# base.net
KiCad netlist of a schematic drawn in EAGLE
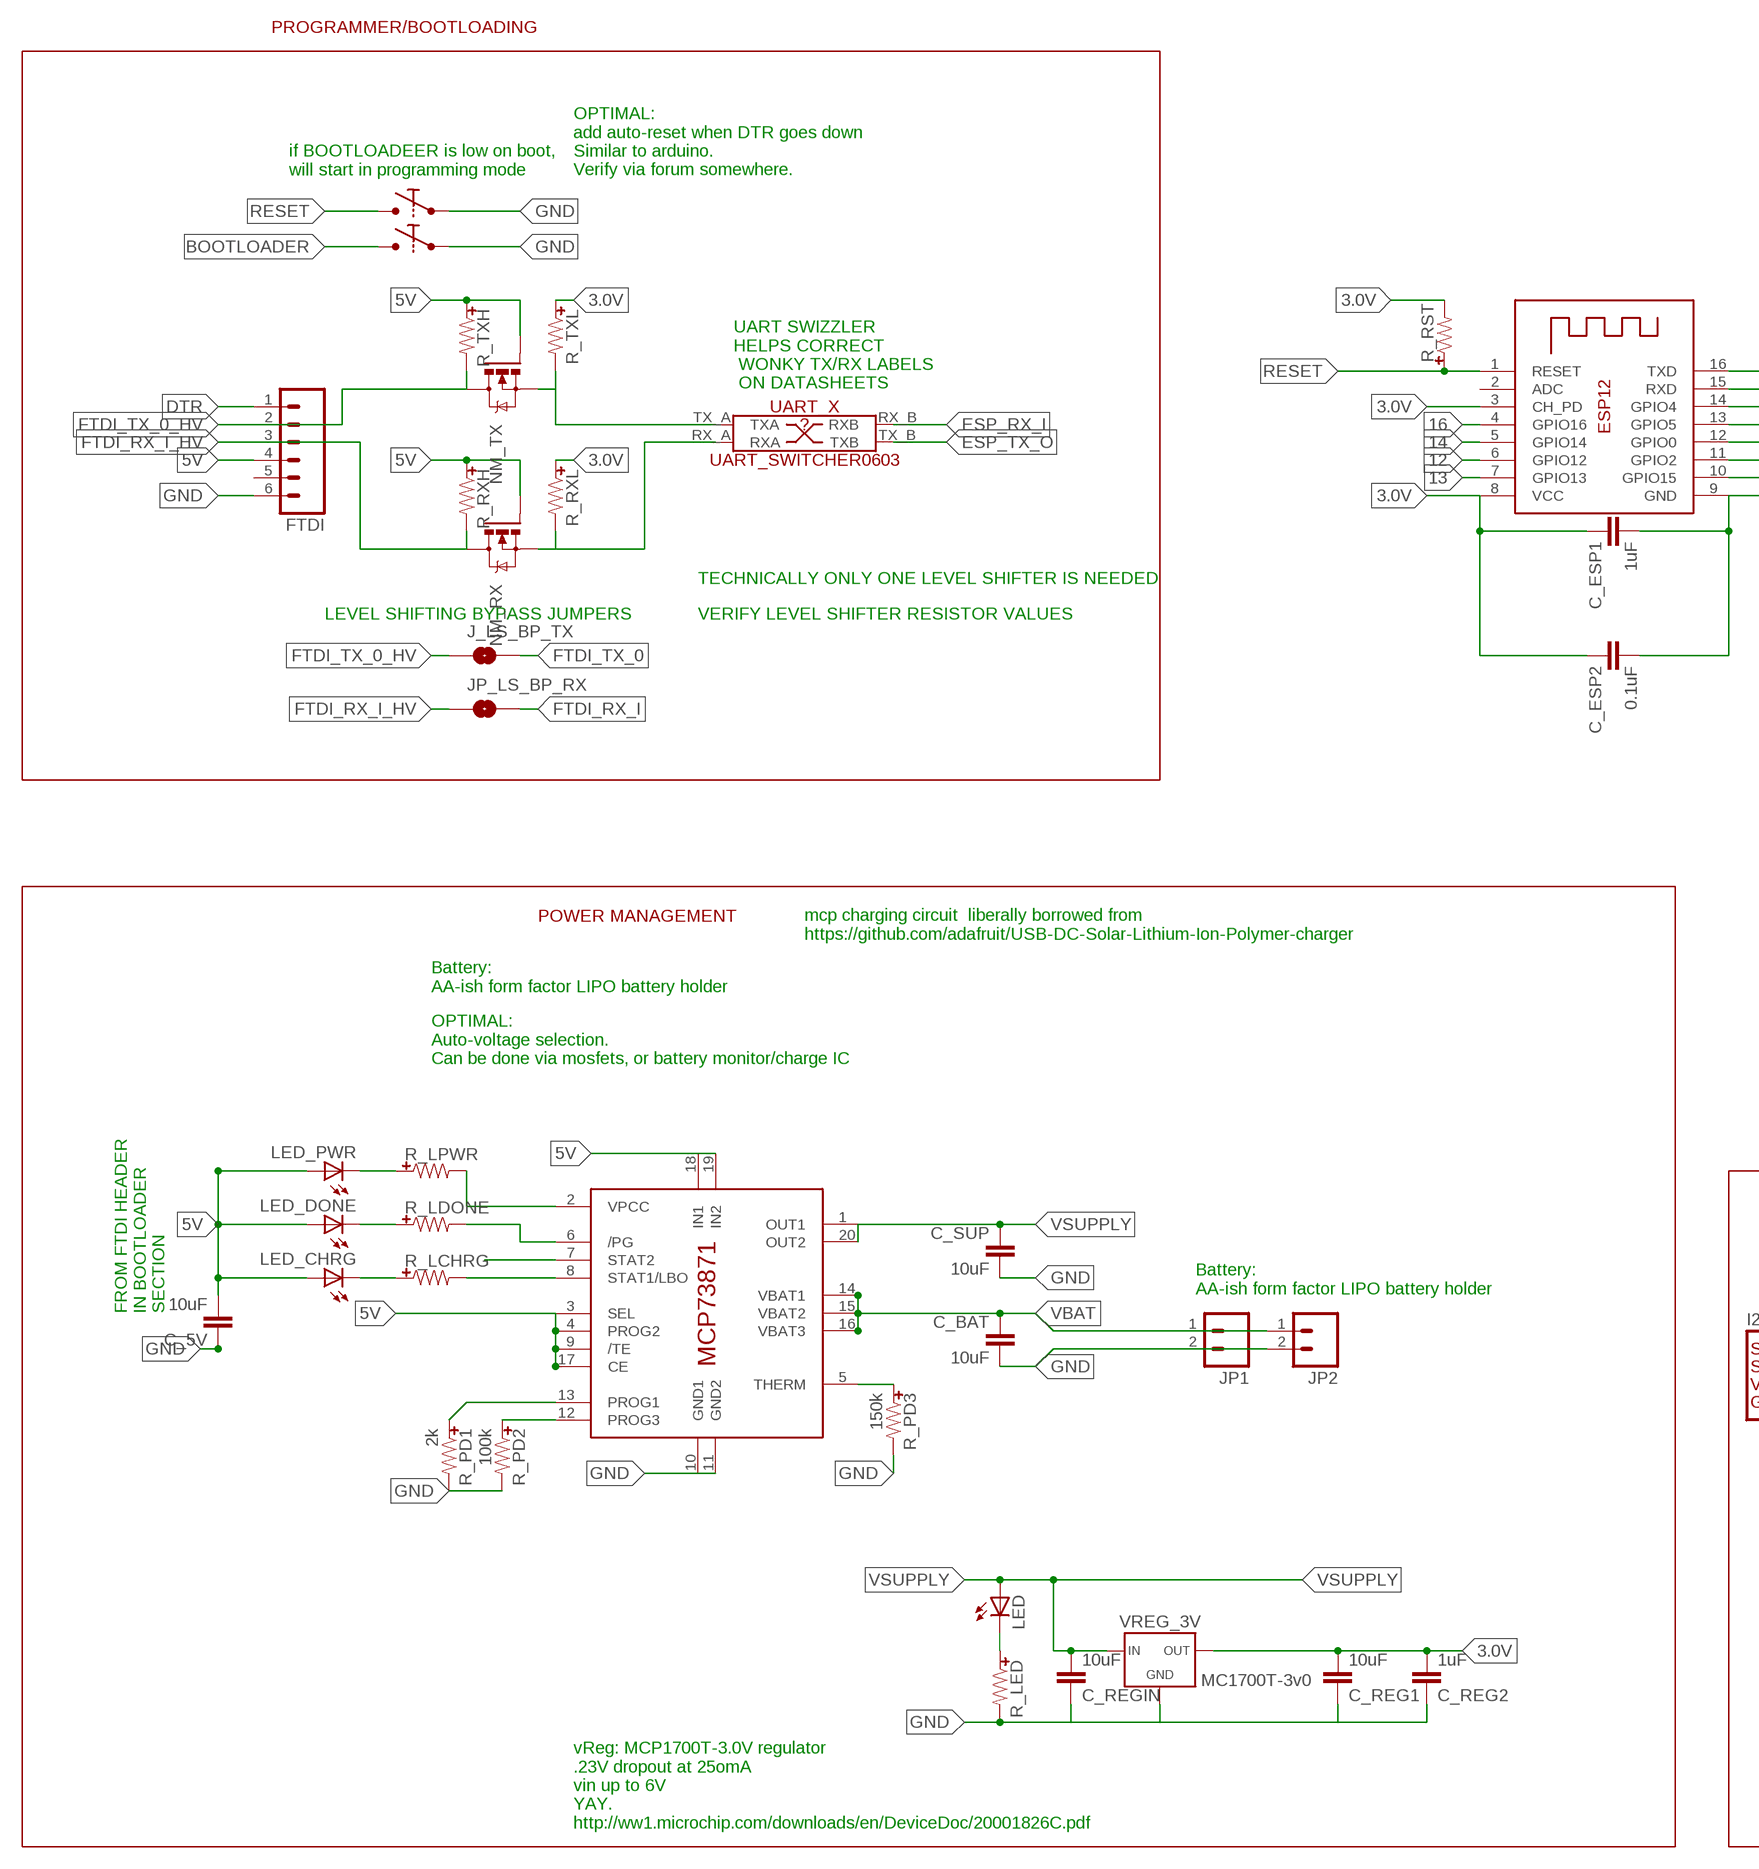
[diagram p0: schematic, sheet 1, part 1 of 2]
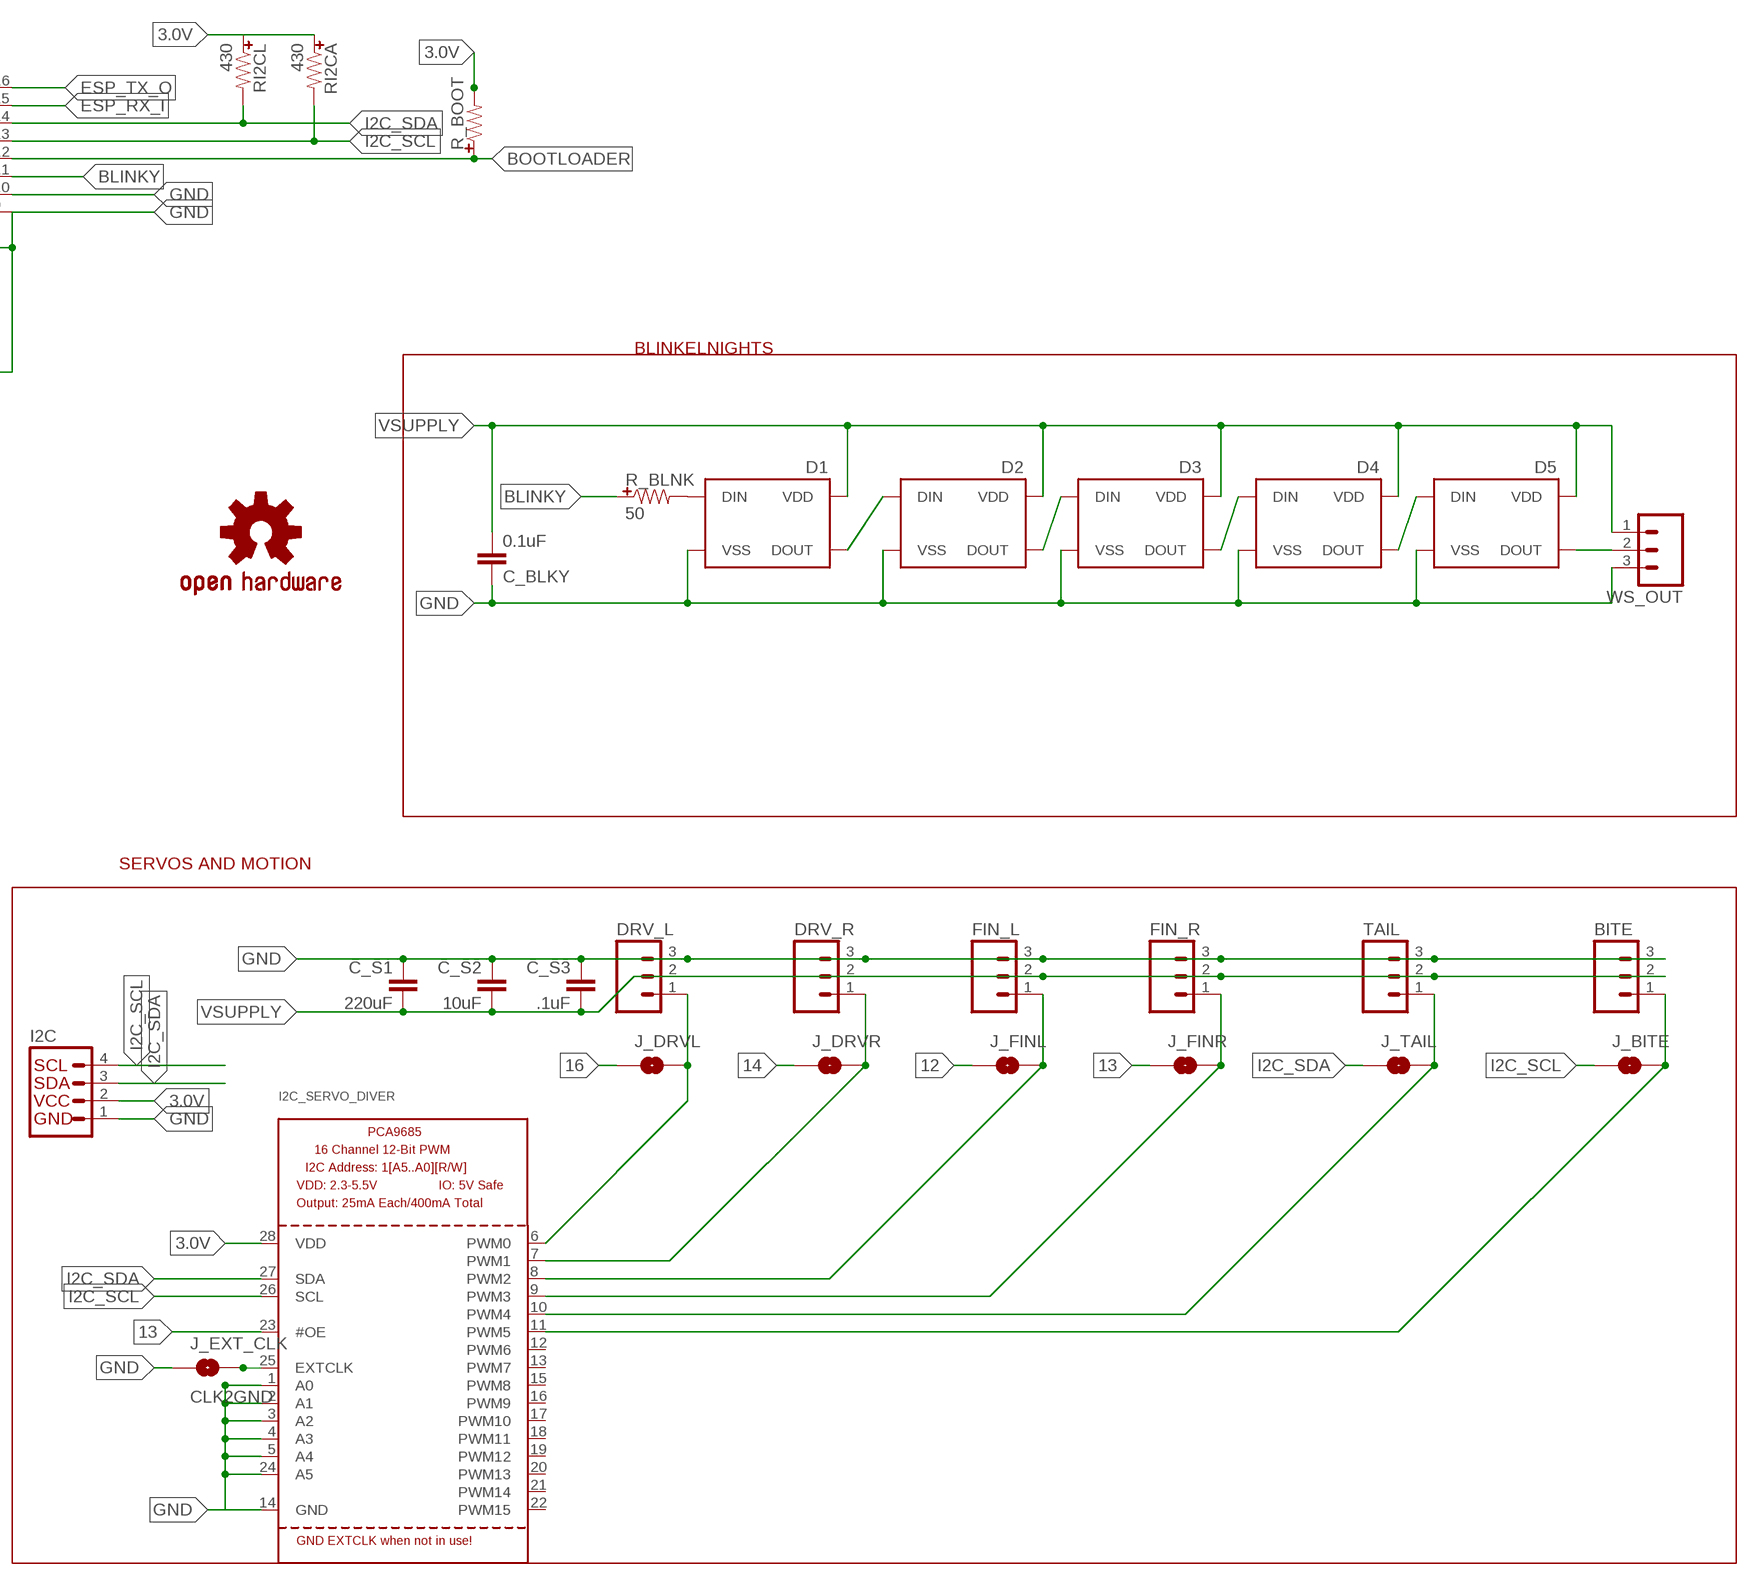
[diagram p1: schematic, sheet 1, part 2 of 2]

(export (version "E")
  (design (tool "Eeschema 10.0.6"))
  (components
    (comp (ref "BITE")
      (value "M03LOCK")
      (footprint "eagle-import:1X03_LOCK")
      (libsource (lib "eagle-import") (part "M03LOCK"))
    )
    (comp (ref "BTN_PROG")
      (value "BUTTONSMD_BUTTON")
      (footprint "eagle-import:SMD_BUTTON")
      (libsource (lib "eagle-import") (part "BUTTONSMD_BUTTON"))
    )
    (comp (ref "BTN_RST")
      (value "BUTTONSMD_BUTTON")
      (footprint "eagle-import:SMD_BUTTON")
      (libsource (lib "eagle-import") (part "BUTTONSMD_BUTTON"))
    )
    (comp (ref "C_5V")
      (value "10uF")
      (footprint "eagle-import:0402-0603-0805-UNIVERSAL")
      (libsource (lib "eagle-import") (part "CAPUNIVERSAL"))
    )
    (comp (ref "C_BAT")
      (value "10uF")
      (footprint "eagle-import:0402-0603-0805-UNIVERSAL")
      (libsource (lib "eagle-import") (part "CAPUNIVERSAL"))
    )
    (comp (ref "C_BLKY")
      (value "0.1uF")
      (footprint "eagle-import:0402-0603-0805-UNIVERSAL")
      (libsource (lib "eagle-import") (part "CAPUNIVERSAL"))
    )
    (comp (ref "C_ESP1")
      (value "1uF")
      (footprint "eagle-import:0402-0603-0805-UNIVERSAL")
      (libsource (lib "eagle-import") (part "CAPUNIVERSAL"))
    )
    (comp (ref "C_ESP2")
      (value "0.1uF")
      (footprint "eagle-import:0402-0603-0805-UNIVERSAL")
      (libsource (lib "eagle-import") (part "CAPUNIVERSAL"))
    )
    (comp (ref "C_REG1")
      (value "10uF")
      (footprint "eagle-import:0402-0603-0805-UNIVERSAL")
      (libsource (lib "eagle-import") (part "CAPUNIVERSAL"))
    )
    (comp (ref "C_REG2")
      (value "1uF")
      (footprint "eagle-import:0402-0603-0805-UNIVERSAL")
      (libsource (lib "eagle-import") (part "CAPUNIVERSAL"))
    )
    (comp (ref "C_REGIN")
      (value "10uF")
      (footprint "eagle-import:0402-0603-0805-UNIVERSAL")
      (libsource (lib "eagle-import") (part "CAPUNIVERSAL"))
    )
    (comp (ref "C_S1")
      (value "220uF")
      (footprint "eagle-import:0402-0603-0805-UNIVERSAL")
      (libsource (lib "eagle-import") (part "CAPUNIVERSAL"))
    )
    (comp (ref "C_S2")
      (value "10uF")
      (footprint "eagle-import:0402-0603-0805-UNIVERSAL")
      (libsource (lib "eagle-import") (part "CAPUNIVERSAL"))
    )
    (comp (ref "C_S3")
      (value ".1uF")
      (footprint "eagle-import:0402-0603-0805-UNIVERSAL")
      (libsource (lib "eagle-import") (part "CAPUNIVERSAL"))
    )
    (comp (ref "C_SUP")
      (value "10uF")
      (footprint "eagle-import:0402-0603-0805-UNIVERSAL")
      (libsource (lib "eagle-import") (part "CAPUNIVERSAL"))
    )
    (comp (ref "D1")
      (value "WS2812B")
      (footprint "eagle-import:WS2812B")
      (libsource (lib "eagle-import") (part "WS2812B"))
    )
    (comp (ref "D2")
      (value "WS2812B")
      (footprint "eagle-import:WS2812B")
      (libsource (lib "eagle-import") (part "WS2812B"))
    )
    (comp (ref "D3")
      (value "WS2812B")
      (footprint "eagle-import:WS2812B")
      (libsource (lib "eagle-import") (part "WS2812B"))
    )
    (comp (ref "D4")
      (value "WS2812B")
      (footprint "eagle-import:WS2812B")
      (libsource (lib "eagle-import") (part "WS2812B"))
    )
    (comp (ref "D5")
      (value "WS2812B")
      (footprint "eagle-import:WS2812B")
      (libsource (lib "eagle-import") (part "WS2812B"))
    )
    (comp (ref "DRV_L")
      (value "M03LOCK")
      (footprint "eagle-import:1X03_LOCK")
      (libsource (lib "eagle-import") (part "M03LOCK"))
    )
    (comp (ref "DRV_R")
      (value "M03LOCK")
      (footprint "eagle-import:1X03_LOCK")
      (libsource (lib "eagle-import") (part "M03LOCK"))
    )
    (comp (ref "FIN_L")
      (value "M03LOCK")
      (footprint "eagle-import:1X03_LOCK")
      (libsource (lib "eagle-import") (part "M03LOCK"))
    )
    (comp (ref "FIN_R")
      (value "M03LOCK")
      (footprint "eagle-import:1X03_LOCK")
      (libsource (lib "eagle-import") (part "M03LOCK"))
    )
    (comp (ref "FTDI")
      (value "M06LOCK")
      (footprint "eagle-import:1X06_LOCK")
      (libsource (lib "eagle-import") (part "M06LOCK"))
    )
    (comp (ref "I2C")
      (value "I2C_STANDARD")
      (footprint "eagle-import:1X04")
      (libsource (lib "eagle-import") (part "I2C_STANDARD"))
    )
    (comp (ref "I2C_SERVO_DIVER")
      (value "PCA9685")
      (footprint "eagle-import:TSSOP28")
      (libsource (lib "eagle-import") (part "PCA9685"))
    )
    (comp (ref "IC_LIPO")
      (value "MCP73871")
      (footprint "eagle-import:QFN20")
      (libsource (lib "eagle-import") (part "MCP73871"))
    )
    (comp (ref "JP1")
      (value "M02JST-PTH-2")
      (footprint "eagle-import:JST-2-PTH")
      (libsource (lib "eagle-import") (part "M02JST-PTH-2"))
    )
    (comp (ref "JP2")
      (value "M02LOCK")
      (footprint "eagle-import:1X02_LOCK")
      (libsource (lib "eagle-import") (part "M02LOCK"))
    )
    (comp (ref "JP_LS_BP_RX")
      (value "JUMPER-PAD-2-NOYES_SILK")
      (footprint "eagle-import:PAD-JUMPER-2-NO_YES_SILK")
      (libsource (lib "eagle-import") (part "JUMPER-PAD-2-NOYES_SILK"))
    )
    (comp (ref "J_BITE")
      (value "JUMPER-PAD-2-NOYES_SILK")
      (footprint "eagle-import:PAD-JUMPER-2-NO_YES_SILK")
      (libsource (lib "eagle-import") (part "JUMPER-PAD-2-NOYES_SILK"))
    )
    (comp (ref "J_DRVL")
      (value "JUMPER-PAD-2-NOYES_SILK")
      (footprint "eagle-import:PAD-JUMPER-2-NO_YES_SILK")
      (libsource (lib "eagle-import") (part "JUMPER-PAD-2-NOYES_SILK"))
    )
    (comp (ref "J_DRVR")
      (value "JUMPER-PAD-2-NOYES_SILK")
      (footprint "eagle-import:PAD-JUMPER-2-NO_YES_SILK")
      (libsource (lib "eagle-import") (part "JUMPER-PAD-2-NOYES_SILK"))
    )
    (comp (ref "J_EXT_CLK")
      (value "CLK2GND")
      (footprint "eagle-import:SJ_2S-TRACE")
      (libsource (lib "eagle-import") (part "SOLDERJUMPERTRACE"))
    )
    (comp (ref "J_FINL")
      (value "JUMPER-PAD-2-NOYES_SILK")
      (footprint "eagle-import:PAD-JUMPER-2-NO_YES_SILK")
      (libsource (lib "eagle-import") (part "JUMPER-PAD-2-NOYES_SILK"))
    )
    (comp (ref "J_FINR")
      (value "JUMPER-PAD-2-NOYES_SILK")
      (footprint "eagle-import:PAD-JUMPER-2-NO_YES_SILK")
      (libsource (lib "eagle-import") (part "JUMPER-PAD-2-NOYES_SILK"))
    )
    (comp (ref "J_LS_BP_TX")
      (value "JUMPER-PAD-2-NOYES_SILK")
      (footprint "eagle-import:PAD-JUMPER-2-NO_YES_SILK")
      (libsource (lib "eagle-import") (part "JUMPER-PAD-2-NOYES_SILK"))
    )
    (comp (ref "J_TAIL")
      (value "JUMPER-PAD-2-NOYES_SILK")
      (footprint "eagle-import:PAD-JUMPER-2-NO_YES_SILK")
      (libsource (lib "eagle-import") (part "JUMPER-PAD-2-NOYES_SILK"))
    )
    (comp (ref "LED")
      (value "LEDUNIVERSAL")
      (footprint "eagle-import:0402-0603-0805-UNIVERSAL")
      (libsource (lib "eagle-import") (part "LEDUNIVERSAL"))
    )
    (comp (ref "LED_CHRG")
      (value "LEDUNIVERSAL")
      (footprint "eagle-import:0402-0603-0805-UNIVERSAL")
      (libsource (lib "eagle-import") (part "LEDUNIVERSAL"))
    )
    (comp (ref "LED_DONE")
      (value "LEDUNIVERSAL")
      (footprint "eagle-import:0402-0603-0805-UNIVERSAL")
      (libsource (lib "eagle-import") (part "LEDUNIVERSAL"))
    )
    (comp (ref "LED_PWR")
      (value "LEDUNIVERSAL")
      (footprint "eagle-import:0402-0603-0805-UNIVERSAL")
      (libsource (lib "eagle-import") (part "LEDUNIVERSAL"))
    )
    (comp (ref "LOGO1")
      (value "OSHW-LOGOS")
      (footprint "eagle-import:OSHW-LOGO-S")
      (libsource (lib "eagle-import") (part "OSHW-LOGOS"))
    )
    (comp (ref "NM_RX")
      (value "MOSFET-NCHANNELSMD")
      (footprint "eagle-import:SOT23-3")
      (libsource (lib "eagle-import") (part "MOSFET-NCHANNELSMD"))
    )
    (comp (ref "NM_TX")
      (value "MOSFET-NCHANNELSMD")
      (footprint "eagle-import:SOT23-3")
      (libsource (lib "eagle-import") (part "MOSFET-NCHANNELSMD"))
    )
    (comp (ref "RI2CA")
      (value "430")
      (footprint "eagle-import:0402-0603-0805-UNIVERSAL")
      (libsource (lib "eagle-import") (part "RESISTORUNIVERSAL"))
    )
    (comp (ref "RI2CL")
      (value "430")
      (footprint "eagle-import:0402-0603-0805-UNIVERSAL")
      (libsource (lib "eagle-import") (part "RESISTORUNIVERSAL"))
    )
    (comp (ref "R_BLNK")
      (value "50")
      (footprint "eagle-import:0402-0603-0805-UNIVERSAL")
      (libsource (lib "eagle-import") (part "RESISTORUNIVERSAL"))
    )
    (comp (ref "R_BOOT")
      (value "RESISTORUNIVERSAL")
      (footprint "eagle-import:0402-0603-0805-UNIVERSAL")
      (libsource (lib "eagle-import") (part "RESISTORUNIVERSAL"))
    )
    (comp (ref "R_LCHRG")
      (value "RESISTORUNIVERSAL")
      (footprint "eagle-import:0402-0603-0805-UNIVERSAL")
      (libsource (lib "eagle-import") (part "RESISTORUNIVERSAL"))
    )
    (comp (ref "R_LDONE")
      (value "RESISTORUNIVERSAL")
      (footprint "eagle-import:0402-0603-0805-UNIVERSAL")
      (libsource (lib "eagle-import") (part "RESISTORUNIVERSAL"))
    )
    (comp (ref "R_LED")
      (value "RESISTORUNIVERSAL")
      (footprint "eagle-import:0402-0603-0805-UNIVERSAL")
      (libsource (lib "eagle-import") (part "RESISTORUNIVERSAL"))
    )
    (comp (ref "R_LPWR")
      (value "RESISTORUNIVERSAL")
      (footprint "eagle-import:0402-0603-0805-UNIVERSAL")
      (libsource (lib "eagle-import") (part "RESISTORUNIVERSAL"))
    )
    (comp (ref "R_PD1")
      (value "2k")
      (footprint "eagle-import:0402-0603-0805-UNIVERSAL")
      (libsource (lib "eagle-import") (part "RESISTORUNIVERSAL"))
    )
    (comp (ref "R_PD2")
      (value "100k")
      (footprint "eagle-import:0402-0603-0805-UNIVERSAL")
      (libsource (lib "eagle-import") (part "RESISTORUNIVERSAL"))
    )
    (comp (ref "R_PD3")
      (value "150k")
      (footprint "eagle-import:0402-0603-0805-UNIVERSAL")
      (libsource (lib "eagle-import") (part "RESISTORUNIVERSAL"))
    )
    (comp (ref "R_RST")
      (value "RESISTORUNIVERSAL")
      (footprint "eagle-import:0402-0603-0805-UNIVERSAL")
      (libsource (lib "eagle-import") (part "RESISTORUNIVERSAL"))
    )
    (comp (ref "R_RXH")
      (value "RESISTORUNIVERSAL")
      (footprint "eagle-import:0402-0603-0805-UNIVERSAL")
      (libsource (lib "eagle-import") (part "RESISTORUNIVERSAL"))
    )
    (comp (ref "R_RXL")
      (value "RESISTORUNIVERSAL")
      (footprint "eagle-import:0402-0603-0805-UNIVERSAL")
      (libsource (lib "eagle-import") (part "RESISTORUNIVERSAL"))
    )
    (comp (ref "R_TXH")
      (value "RESISTORUNIVERSAL")
      (footprint "eagle-import:0402-0603-0805-UNIVERSAL")
      (libsource (lib "eagle-import") (part "RESISTORUNIVERSAL"))
    )
    (comp (ref "R_TXL")
      (value "RESISTORUNIVERSAL")
      (footprint "eagle-import:0402-0603-0805-UNIVERSAL")
      (libsource (lib "eagle-import") (part "RESISTORUNIVERSAL"))
    )
    (comp (ref "TAIL")
      (value "M03LOCK")
      (footprint "eagle-import:1X03_LOCK")
      (libsource (lib "eagle-import") (part "M03LOCK"))
    )
    (comp (ref "UART_X")
      (value "UART_SWITCHER0603")
      (footprint "eagle-import:UART_SWITCHER_0603")
      (libsource (lib "eagle-import") (part "UART_SWITCHER0603"))
    )
    (comp (ref "VREG_3V")
      (value "MC1700T-3v0")
      (footprint "eagle-import:SOT23")
      (libsource (lib "eagle-import") (part "VOLTAGE-REGULATORMCP1703"))
    )
    (comp (ref "WS_OUT")
      (value "M03LOCK")
      (footprint "eagle-import:1X03_LOCK")
      (libsource (lib "eagle-import") (part "M03LOCK"))
    )
    (comp (ref "X1")
      (value "ESP-12")
      (footprint "eagle-import:ESP-12")
      (libsource (lib "eagle-import") (part "ESP-12"))
    )
  )
  (nets
    (net (code "1") (name "3.0V") (class "Default")
      (node (ref "C_ESP1") (pin "-") (pinfunction "1_-") (pintype "passive"))
      (node (ref "C_ESP2") (pin "-") (pinfunction "1_-") (pintype "passive"))
      (node (ref "C_REG1") (pin "+") (pinfunction "2_+") (pintype "passive"))
      (node (ref "C_REG2") (pin "+") (pinfunction "2_+") (pintype "passive"))
      (node (ref "I2C") (pin "2") (pinfunction "2_2") (pintype "passive"))
      (node (ref "I2C_SERVO_DIVER") (pin "28") (pinfunction "VDD_28") (pintype "power_in"))
      (node (ref "RI2CA") (pin "+") (pinfunction "1_+") (pintype "passive"))
      (node (ref "RI2CL") (pin "+") (pinfunction "1_+") (pintype "passive"))
      (node (ref "R_BOOT") (pin "-") (pinfunction "2_-") (pintype "passive"))
      (node (ref "R_RST") (pin "-") (pinfunction "2_-") (pintype "passive"))
      (node (ref "R_RXL") (pin "+") (pinfunction "1_+") (pintype "passive"))
      (node (ref "R_TXL") (pin "+") (pinfunction "1_+") (pintype "passive"))
      (node (ref "VREG_3V") (pin "2") (pinfunction "OUT_2") (pintype "input"))
      (node (ref "X1") (pin "3") (pinfunction "CH_PD_3") (pintype "input"))
      (node (ref "X1") (pin "8") (pinfunction "VCC_8") (pintype "power_in"))
    )
    (net (code "2") (name "5V") (class "Default")
      (node (ref "C_5V") (pin "+") (pinfunction "2_+") (pintype "passive"))
      (node (ref "FTDI") (pin "4") (pinfunction "4_4") (pintype "passive"))
      (node (ref "IC_LIPO") (pin "17") (pinfunction "CE_17") (pintype "input"))
      (node (ref "IC_LIPO") (pin "18") (pinfunction "IN1_18") (pintype "input"))
      (node (ref "IC_LIPO") (pin "19") (pinfunction "IN2_19") (pintype "input"))
      (node (ref "IC_LIPO") (pin "3") (pinfunction "SEL_3") (pintype "input"))
      (node (ref "IC_LIPO") (pin "4") (pinfunction "PROG2_4") (pintype "input"))
      (node (ref "IC_LIPO") (pin "9") (pinfunction "/TE_9") (pintype "input"))
      (node (ref "LED_CHRG") (pin "+") (pinfunction "A_+") (pintype "passive"))
      (node (ref "LED_DONE") (pin "+") (pinfunction "A_+") (pintype "passive"))
      (node (ref "LED_PWR") (pin "+") (pinfunction "A_+") (pintype "passive"))
      (node (ref "NM_RX") (pin "1") (pinfunction "G_1") (pintype "passive"))
      (node (ref "NM_TX") (pin "1") (pinfunction "G_1") (pintype "passive"))
      (node (ref "R_RXH") (pin "+") (pinfunction "1_+") (pintype "passive"))
      (node (ref "R_TXH") (pin "+") (pinfunction "1_+") (pintype "passive"))
    )
    (net (code "3") (name "12") (class "Default")
      (node (ref "J_FINL") (pin "1") (pinfunction "1_1") (pintype "passive"))
      (node (ref "X1") (pin "6") (pinfunction "GPIO12_6") (pintype "bidirectional"))
    )
    (net (code "4") (name "13") (class "Default")
      (node (ref "I2C_SERVO_DIVER") (pin "23") (pinfunction "#OE_23") (pintype "input"))
      (node (ref "J_FINR") (pin "1") (pinfunction "1_1") (pintype "passive"))
      (node (ref "X1") (pin "7") (pinfunction "GPIO13_7") (pintype "bidirectional"))
    )
    (net (code "5") (name "14") (class "Default")
      (node (ref "J_DRVR") (pin "1") (pinfunction "1_1") (pintype "passive"))
      (node (ref "X1") (pin "5") (pinfunction "GPIO14_5") (pintype "bidirectional"))
    )
    (net (code "6") (name "16") (class "Default")
      (node (ref "J_DRVL") (pin "1") (pinfunction "1_1") (pintype "passive"))
      (node (ref "X1") (pin "4") (pinfunction "GPIO16_4") (pintype "bidirectional"))
    )
    (net (code "7") (name "BLINKY") (class "Default")
      (node (ref "R_BLNK") (pin "+") (pinfunction "1_+") (pintype "passive"))
      (node (ref "X1") (pin "11") (pinfunction "GPIO2_11") (pintype "bidirectional"))
    )
    (net (code "8") (name "BOOTLOADER") (class "Default")
      (node (ref "BTN_PROG") (pin "P$1") (pinfunction "P$1_P$1") (pintype "bidirectional"))
      (node (ref "BTN_PROG") (pin "P$2") (pinfunction "P$1_P$2") (pintype "bidirectional"))
      (node (ref "R_BOOT") (pin "+") (pinfunction "1_+") (pintype "passive"))
      (node (ref "X1") (pin "12") (pinfunction "GPIO0_12") (pintype "bidirectional"))
    )
    (net (code "9") (name "DTR") (class "Default")
      (node (ref "FTDI") (pin "1") (pinfunction "1_1") (pintype "passive"))
    )
    (net (code "10") (name "ESP_RX_I") (class "Default")
      (node (ref "UART_X") (pin "RX_B") (pinfunction "RXB_RX_B") (pintype "bidirectional"))
      (node (ref "X1") (pin "15") (pinfunction "RXD_15") (pintype "input"))
    )
    (net (code "11") (name "ESP_TX_O") (class "Default")
      (node (ref "UART_X") (pin "TX_B") (pinfunction "TXB_TX_B") (pintype "bidirectional"))
      (node (ref "X1") (pin "16") (pinfunction "TXD_16") (pintype "output"))
    )
    (net (code "12") (name "FTDI_RX_I") (class "Default")
      (node (ref "JP_LS_BP_RX") (pin "2") (pinfunction "2_2") (pintype "passive"))
      (node (ref "NM_RX") (pin "2") (pinfunction "S_2") (pintype "passive"))
      (node (ref "R_RXL") (pin "-") (pinfunction "2_-") (pintype "passive"))
      (node (ref "UART_X") (pin "RX_A") (pinfunction "RXA_RX_A") (pintype "bidirectional"))
    )
    (net (code "13") (name "FTDI_RX_I_HV") (class "Default")
      (node (ref "FTDI") (pin "3") (pinfunction "3_3") (pintype "passive"))
      (node (ref "JP_LS_BP_RX") (pin "1") (pinfunction "1_1") (pintype "passive"))
      (node (ref "NM_RX") (pin "3") (pinfunction "D_3") (pintype "passive"))
      (node (ref "R_RXH") (pin "-") (pinfunction "2_-") (pintype "passive"))
    )
    (net (code "14") (name "FTDI_TX_0") (class "Default")
      (node (ref "J_LS_BP_TX") (pin "2") (pinfunction "2_2") (pintype "passive"))
      (node (ref "NM_TX") (pin "2") (pinfunction "S_2") (pintype "passive"))
      (node (ref "R_TXL") (pin "-") (pinfunction "2_-") (pintype "passive"))
      (node (ref "UART_X") (pin "TX_A") (pinfunction "TXA_TX_A") (pintype "bidirectional"))
    )
    (net (code "15") (name "FTDI_TX_0_HV") (class "Default")
      (node (ref "FTDI") (pin "2") (pinfunction "2_2") (pintype "passive"))
      (node (ref "J_LS_BP_TX") (pin "1") (pinfunction "1_1") (pintype "passive"))
      (node (ref "NM_TX") (pin "3") (pinfunction "D_3") (pintype "passive"))
      (node (ref "R_TXH") (pin "-") (pinfunction "2_-") (pintype "passive"))
    )
    (net (code "16") (name "GND") (class "Default")
      (node (ref "BITE") (pin "3") (pinfunction "3_3") (pintype "passive"))
      (node (ref "BTN_PROG") (pin "P$3") (pinfunction "P$2_P$3") (pintype "bidirectional"))
      (node (ref "BTN_PROG") (pin "P$4") (pinfunction "P$2_P$4") (pintype "bidirectional"))
      (node (ref "BTN_RST") (pin "P$3") (pinfunction "P$2_P$3") (pintype "bidirectional"))
      (node (ref "BTN_RST") (pin "P$4") (pinfunction "P$2_P$4") (pintype "bidirectional"))
      (node (ref "C_5V") (pin "-") (pinfunction "1_-") (pintype "passive"))
      (node (ref "C_BAT") (pin "+") (pinfunction "2_+") (pintype "passive"))
      (node (ref "C_BLKY") (pin "-") (pinfunction "1_-") (pintype "passive"))
      (node (ref "C_ESP1") (pin "+") (pinfunction "2_+") (pintype "passive"))
      (node (ref "C_ESP2") (pin "+") (pinfunction "2_+") (pintype "passive"))
      (node (ref "C_REG1") (pin "-") (pinfunction "1_-") (pintype "passive"))
      (node (ref "C_REG2") (pin "-") (pinfunction "1_-") (pintype "passive"))
      (node (ref "C_REGIN") (pin "-") (pinfunction "1_-") (pintype "passive"))
      (node (ref "C_S1") (pin "-") (pinfunction "1_-") (pintype "passive"))
      (node (ref "C_S2") (pin "-") (pinfunction "1_-") (pintype "passive"))
      (node (ref "C_S3") (pin "-") (pinfunction "1_-") (pintype "passive"))
      (node (ref "C_SUP") (pin "+") (pinfunction "2_+") (pintype "passive"))
      (node (ref "D1") (pin "3") (pinfunction "VSS_3") (pintype "power_in"))
      (node (ref "D2") (pin "3") (pinfunction "VSS_3") (pintype "power_in"))
      (node (ref "D3") (pin "3") (pinfunction "VSS_3") (pintype "power_in"))
      (node (ref "D4") (pin "3") (pinfunction "VSS_3") (pintype "power_in"))
      (node (ref "D5") (pin "3") (pinfunction "VSS_3") (pintype "power_in"))
      (node (ref "DRV_L") (pin "3") (pinfunction "3_3") (pintype "passive"))
      (node (ref "DRV_R") (pin "3") (pinfunction "3_3") (pintype "passive"))
      (node (ref "FIN_L") (pin "3") (pinfunction "3_3") (pintype "passive"))
      (node (ref "FIN_R") (pin "3") (pinfunction "3_3") (pintype "passive"))
      (node (ref "FTDI") (pin "6") (pinfunction "6_6") (pintype "passive"))
      (node (ref "I2C") (pin "1") (pinfunction "1_1") (pintype "passive"))
      (node (ref "I2C_SERVO_DIVER") (pin "1") (pinfunction "A0_1") (pintype "bidirectional"))
      (node (ref "I2C_SERVO_DIVER") (pin "14") (pinfunction "GND_14") (pintype "power_in"))
      (node (ref "I2C_SERVO_DIVER") (pin "2") (pinfunction "A1_2") (pintype "bidirectional"))
      (node (ref "I2C_SERVO_DIVER") (pin "24") (pinfunction "A5_24") (pintype "bidirectional"))
      (node (ref "I2C_SERVO_DIVER") (pin "3") (pinfunction "A2_3") (pintype "bidirectional"))
      (node (ref "I2C_SERVO_DIVER") (pin "4") (pinfunction "A3_4") (pintype "bidirectional"))
      (node (ref "I2C_SERVO_DIVER") (pin "5") (pinfunction "A4_5") (pintype "bidirectional"))
      (node (ref "IC_LIPO") (pin "10") (pinfunction "GND1_10") (pintype "power_in"))
      (node (ref "IC_LIPO") (pin "11") (pinfunction "GND2_11") (pintype "power_in"))
      (node (ref "JP1") (pin "2") (pinfunction "2_2") (pintype "passive"))
      (node (ref "JP2") (pin "2") (pinfunction "2_2") (pintype "passive"))
      (node (ref "J_EXT_CLK") (pin "1") (pinfunction "1_1") (pintype "passive"))
      (node (ref "R_LED") (pin "-") (pinfunction "2_-") (pintype "passive"))
      (node (ref "R_PD1") (pin "-") (pinfunction "2_-") (pintype "passive"))
      (node (ref "R_PD2") (pin "-") (pinfunction "2_-") (pintype "passive"))
      (node (ref "R_PD3") (pin "-") (pinfunction "2_-") (pintype "passive"))
      (node (ref "TAIL") (pin "3") (pinfunction "3_3") (pintype "passive"))
      (node (ref "VREG_3V") (pin "1") (pinfunction "GND_1") (pintype "input"))
      (node (ref "WS_OUT") (pin "3") (pinfunction "3_3") (pintype "passive"))
      (node (ref "X1") (pin "10") (pinfunction "GPIO15_10") (pintype "bidirectional"))
      (node (ref "X1") (pin "9") (pinfunction "GND_9") (pintype "power_in"))
    )
    (net (code "17") (name "I2C_SCL") (class "Default")
      (node (ref "I2C") (pin "4") (pinfunction "4_4") (pintype "passive"))
      (node (ref "I2C_SERVO_DIVER") (pin "26") (pinfunction "SCL_26") (pintype "bidirectional"))
      (node (ref "J_BITE") (pin "1") (pinfunction "1_1") (pintype "passive"))
      (node (ref "RI2CA") (pin "-") (pinfunction "2_-") (pintype "passive"))
      (node (ref "X1") (pin "13") (pinfunction "GPIO5_13") (pintype "bidirectional"))
    )
    (net (code "18") (name "I2C_SDA") (class "Default")
      (node (ref "I2C") (pin "3") (pinfunction "3_3") (pintype "passive"))
      (node (ref "I2C_SERVO_DIVER") (pin "27") (pinfunction "SDA_27") (pintype "bidirectional"))
      (node (ref "J_TAIL") (pin "1") (pinfunction "1_1") (pintype "passive"))
      (node (ref "RI2CL") (pin "-") (pinfunction "2_-") (pintype "passive"))
      (node (ref "X1") (pin "14") (pinfunction "GPIO4_14") (pintype "bidirectional"))
    )
    (net (code "19") (name "Net-(D1-DIN)") (class "Default")
      (node (ref "D1") (pin "4") (pinfunction "DIN_4") (pintype "input"))
      (node (ref "R_BLNK") (pin "-") (pinfunction "2_-") (pintype "passive"))
    )
    (net (code "20") (name "Net-(D1-DOUT)") (class "Default")
      (node (ref "D1") (pin "2") (pinfunction "DOUT_2") (pintype "output"))
      (node (ref "D2") (pin "4") (pinfunction "DIN_4") (pintype "input"))
    )
    (net (code "21") (name "Net-(D2-DOUT)") (class "Default")
      (node (ref "D2") (pin "2") (pinfunction "DOUT_2") (pintype "output"))
      (node (ref "D3") (pin "4") (pinfunction "DIN_4") (pintype "input"))
    )
    (net (code "22") (name "Net-(D3-DOUT)") (class "Default")
      (node (ref "D3") (pin "2") (pinfunction "DOUT_2") (pintype "output"))
      (node (ref "D4") (pin "4") (pinfunction "DIN_4") (pintype "input"))
    )
    (net (code "23") (name "Net-(D4-DOUT)") (class "Default")
      (node (ref "D4") (pin "2") (pinfunction "DOUT_2") (pintype "output"))
      (node (ref "D5") (pin "4") (pinfunction "DIN_4") (pintype "input"))
    )
    (net (code "24") (name "Net-(D5-DOUT)") (class "Default")
      (node (ref "D5") (pin "2") (pinfunction "DOUT_2") (pintype "output"))
      (node (ref "WS_OUT") (pin "2") (pinfunction "2_2") (pintype "passive"))
    )
    (net (code "25") (name "Net-(I2C_SERVO_DIVER-EXTCLK)") (class "Default")
      (node (ref "I2C_SERVO_DIVER") (pin "25") (pinfunction "EXTCLK_25") (pintype "input"))
      (node (ref "J_EXT_CLK") (pin "2") (pinfunction "2_2") (pintype "passive"))
    )
    (net (code "26") (name "Net-(I2C_SERVO_DIVER-PWM0)") (class "Default")
      (node (ref "DRV_L") (pin "1") (pinfunction "1_1") (pintype "passive"))
      (node (ref "I2C_SERVO_DIVER") (pin "6") (pinfunction "PWM0_6") (pintype "output"))
      (node (ref "J_DRVL") (pin "2") (pinfunction "2_2") (pintype "passive"))
    )
    (net (code "27") (name "Net-(I2C_SERVO_DIVER-PWM1)") (class "Default")
      (node (ref "DRV_R") (pin "1") (pinfunction "1_1") (pintype "passive"))
      (node (ref "I2C_SERVO_DIVER") (pin "7") (pinfunction "PWM1_7") (pintype "output"))
      (node (ref "J_DRVR") (pin "2") (pinfunction "2_2") (pintype "passive"))
    )
    (net (code "28") (name "Net-(I2C_SERVO_DIVER-PWM2)") (class "Default")
      (node (ref "FIN_L") (pin "1") (pinfunction "1_1") (pintype "passive"))
      (node (ref "I2C_SERVO_DIVER") (pin "8") (pinfunction "PWM2_8") (pintype "output"))
      (node (ref "J_FINL") (pin "2") (pinfunction "2_2") (pintype "passive"))
    )
    (net (code "29") (name "Net-(I2C_SERVO_DIVER-PWM3)") (class "Default")
      (node (ref "FIN_R") (pin "1") (pinfunction "1_1") (pintype "passive"))
      (node (ref "I2C_SERVO_DIVER") (pin "9") (pinfunction "PWM3_9") (pintype "output"))
      (node (ref "J_FINR") (pin "2") (pinfunction "2_2") (pintype "passive"))
    )
    (net (code "30") (name "Net-(I2C_SERVO_DIVER-PWM4)") (class "Default")
      (node (ref "I2C_SERVO_DIVER") (pin "10") (pinfunction "PWM4_10") (pintype "output"))
      (node (ref "J_TAIL") (pin "2") (pinfunction "2_2") (pintype "passive"))
      (node (ref "TAIL") (pin "1") (pinfunction "1_1") (pintype "passive"))
    )
    (net (code "31") (name "Net-(I2C_SERVO_DIVER-PWM5)") (class "Default")
      (node (ref "BITE") (pin "1") (pinfunction "1_1") (pintype "passive"))
      (node (ref "I2C_SERVO_DIVER") (pin "11") (pinfunction "PWM5_11") (pintype "output"))
      (node (ref "J_BITE") (pin "2") (pinfunction "2_2") (pintype "passive"))
    )
    (net (code "32") (name "Net-(IC_LIPO-PROG1)") (class "Default")
      (node (ref "IC_LIPO") (pin "13") (pinfunction "PROG1_13") (pintype "input"))
      (node (ref "R_PD1") (pin "+") (pinfunction "1_+") (pintype "passive"))
    )
    (net (code "33") (name "Net-(IC_LIPO-PROG3)") (class "Default")
      (node (ref "IC_LIPO") (pin "12") (pinfunction "PROG3_12") (pintype "input"))
      (node (ref "R_PD2") (pin "+") (pinfunction "1_+") (pintype "passive"))
    )
    (net (code "34") (name "Net-(IC_LIPO-STAT1{slash}LBO)") (class "Default")
      (node (ref "IC_LIPO") (pin "8") (pinfunction "STAT1/LBO_8") (pintype "output"))
      (node (ref "R_LCHRG") (pin "-") (pinfunction "2_-") (pintype "passive"))
    )
    (net (code "35") (name "Net-(IC_LIPO-THERM)") (class "Default")
      (node (ref "IC_LIPO") (pin "5") (pinfunction "THERM_5") (pintype "input"))
      (node (ref "R_PD3") (pin "+") (pinfunction "1_+") (pintype "passive"))
    )
    (net (code "36") (name "Net-(IC_LIPO-VPCC)") (class "Default")
      (node (ref "IC_LIPO") (pin "2") (pinfunction "VPCC_2") (pintype "input"))
      (node (ref "R_LPWR") (pin "-") (pinfunction "2_-") (pintype "passive"))
    )
    (net (code "37") (name "Net-(IC_LIPO-{slash}PG)") (class "Default")
      (node (ref "IC_LIPO") (pin "6") (pinfunction "/PG_6") (pintype "output"))
      (node (ref "R_LDONE") (pin "-") (pinfunction "2_-") (pintype "passive"))
    )
    (net (code "38") (name "Net-(LED-C)") (class "Default")
      (node (ref "LED") (pin "-") (pinfunction "C_-") (pintype "passive"))
      (node (ref "R_LED") (pin "+") (pinfunction "1_+") (pintype "passive"))
    )
    (net (code "39") (name "Net-(LED_CHRG-C)") (class "Default")
      (node (ref "LED_CHRG") (pin "-") (pinfunction "C_-") (pintype "passive"))
      (node (ref "R_LCHRG") (pin "+") (pinfunction "1_+") (pintype "passive"))
    )
    (net (code "40") (name "Net-(LED_DONE-C)") (class "Default")
      (node (ref "LED_DONE") (pin "-") (pinfunction "C_-") (pintype "passive"))
      (node (ref "R_LDONE") (pin "+") (pinfunction "1_+") (pintype "passive"))
    )
    (net (code "41") (name "Net-(LED_PWR-C)") (class "Default")
      (node (ref "LED_PWR") (pin "-") (pinfunction "C_-") (pintype "passive"))
      (node (ref "R_LPWR") (pin "+") (pinfunction "1_+") (pintype "passive"))
    )
    (net (code "42") (name "RESET") (class "Default")
      (node (ref "BTN_RST") (pin "P$1") (pinfunction "P$1_P$1") (pintype "bidirectional"))
      (node (ref "BTN_RST") (pin "P$2") (pinfunction "P$1_P$2") (pintype "bidirectional"))
      (node (ref "R_RST") (pin "+") (pinfunction "1_+") (pintype "passive"))
      (node (ref "X1") (pin "1") (pinfunction "RESET_1") (pintype "input"))
    )
    (net (code "43") (name "VBAT") (class "Default")
      (node (ref "C_BAT") (pin "-") (pinfunction "1_-") (pintype "passive"))
      (node (ref "IC_LIPO") (pin "14") (pinfunction "VBAT1_14") (pintype "output"))
      (node (ref "IC_LIPO") (pin "15") (pinfunction "VBAT2_15") (pintype "output"))
      (node (ref "IC_LIPO") (pin "16") (pinfunction "VBAT3_16") (pintype "output"))
      (node (ref "JP1") (pin "1") (pinfunction "1_1") (pintype "passive"))
      (node (ref "JP2") (pin "1") (pinfunction "1_1") (pintype "passive"))
    )
    (net (code "44") (name "VSUPPLY") (class "Default")
      (node (ref "BITE") (pin "2") (pinfunction "2_2") (pintype "passive"))
      (node (ref "C_BLKY") (pin "+") (pinfunction "2_+") (pintype "passive"))
      (node (ref "C_REGIN") (pin "+") (pinfunction "2_+") (pintype "passive"))
      (node (ref "C_S1") (pin "+") (pinfunction "2_+") (pintype "passive"))
      (node (ref "C_S2") (pin "+") (pinfunction "2_+") (pintype "passive"))
      (node (ref "C_S3") (pin "+") (pinfunction "2_+") (pintype "passive"))
      (node (ref "C_SUP") (pin "-") (pinfunction "1_-") (pintype "passive"))
      (node (ref "D1") (pin "1") (pinfunction "VDD_1") (pintype "power_in"))
      (node (ref "D2") (pin "1") (pinfunction "VDD_1") (pintype "power_in"))
      (node (ref "D3") (pin "1") (pinfunction "VDD_1") (pintype "power_in"))
      (node (ref "D4") (pin "1") (pinfunction "VDD_1") (pintype "power_in"))
      (node (ref "D5") (pin "1") (pinfunction "VDD_1") (pintype "power_in"))
      (node (ref "DRV_L") (pin "2") (pinfunction "2_2") (pintype "passive"))
      (node (ref "DRV_R") (pin "2") (pinfunction "2_2") (pintype "passive"))
      (node (ref "FIN_L") (pin "2") (pinfunction "2_2") (pintype "passive"))
      (node (ref "FIN_R") (pin "2") (pinfunction "2_2") (pintype "passive"))
      (node (ref "IC_LIPO") (pin "1") (pinfunction "OUT1_1") (pintype "output"))
      (node (ref "IC_LIPO") (pin "20") (pinfunction "OUT2_20") (pintype "output"))
      (node (ref "LED") (pin "+") (pinfunction "A_+") (pintype "passive"))
      (node (ref "TAIL") (pin "2") (pinfunction "2_2") (pintype "passive"))
      (node (ref "VREG_3V") (pin "3") (pinfunction "IN_3") (pintype "input"))
      (node (ref "WS_OUT") (pin "1") (pinfunction "1_1") (pintype "passive"))
    )
    (net (code "45") (name "unconnected-(FTDI-Pad5)") (class "Default")
      (node (ref "FTDI") (pin "5") (pinfunction "5_5") (pintype "passive"))
    )
    (net (code "46") (name "unconnected-(I2C_SERVO_DIVER-PWM6-Pad12)") (class "Default")
      (node (ref "I2C_SERVO_DIVER") (pin "12") (pinfunction "PWM6_12") (pintype "output"))
    )
    (net (code "47") (name "unconnected-(I2C_SERVO_DIVER-PWM7-Pad13)") (class "Default")
      (node (ref "I2C_SERVO_DIVER") (pin "13") (pinfunction "PWM7_13") (pintype "output"))
    )
    (net (code "48") (name "unconnected-(I2C_SERVO_DIVER-PWM8-Pad15)") (class "Default")
      (node (ref "I2C_SERVO_DIVER") (pin "15") (pinfunction "PWM8_15") (pintype "output"))
    )
    (net (code "49") (name "unconnected-(I2C_SERVO_DIVER-PWM9-Pad16)") (class "Default")
      (node (ref "I2C_SERVO_DIVER") (pin "16") (pinfunction "PWM9_16") (pintype "output"))
    )
    (net (code "50") (name "unconnected-(I2C_SERVO_DIVER-PWM10-Pad17)") (class "Default")
      (node (ref "I2C_SERVO_DIVER") (pin "17") (pinfunction "PWM10_17") (pintype "output"))
    )
    (net (code "51") (name "unconnected-(I2C_SERVO_DIVER-PWM11-Pad18)") (class "Default")
      (node (ref "I2C_SERVO_DIVER") (pin "18") (pinfunction "PWM11_18") (pintype "output"))
    )
    (net (code "52") (name "unconnected-(I2C_SERVO_DIVER-PWM12-Pad19)") (class "Default")
      (node (ref "I2C_SERVO_DIVER") (pin "19") (pinfunction "PWM12_19") (pintype "output"))
    )
    (net (code "53") (name "unconnected-(I2C_SERVO_DIVER-PWM13-Pad20)") (class "Default")
      (node (ref "I2C_SERVO_DIVER") (pin "20") (pinfunction "PWM13_20") (pintype "output"))
    )
    (net (code "54") (name "unconnected-(I2C_SERVO_DIVER-PWM14-Pad21)") (class "Default")
      (node (ref "I2C_SERVO_DIVER") (pin "21") (pinfunction "PWM14_21") (pintype "output"))
    )
    (net (code "55") (name "unconnected-(I2C_SERVO_DIVER-PWM15-Pad22)") (class "Default")
      (node (ref "I2C_SERVO_DIVER") (pin "22") (pinfunction "PWM15_22") (pintype "output"))
    )
    (net (code "56") (name "unconnected-(IC_LIPO-STAT2-Pad7)") (class "Default")
      (node (ref "IC_LIPO") (pin "7") (pinfunction "STAT2_7") (pintype "output"))
    )
    (net (code "57") (name "unconnected-(X1-ADC-Pad2)") (class "Default")
      (node (ref "X1") (pin "2") (pinfunction "ADC_2") (pintype "passive"))
    )
  )
)
